# BatMeas5_3_JST.net
KiCad netlist of a schematic drawn in EAGLE
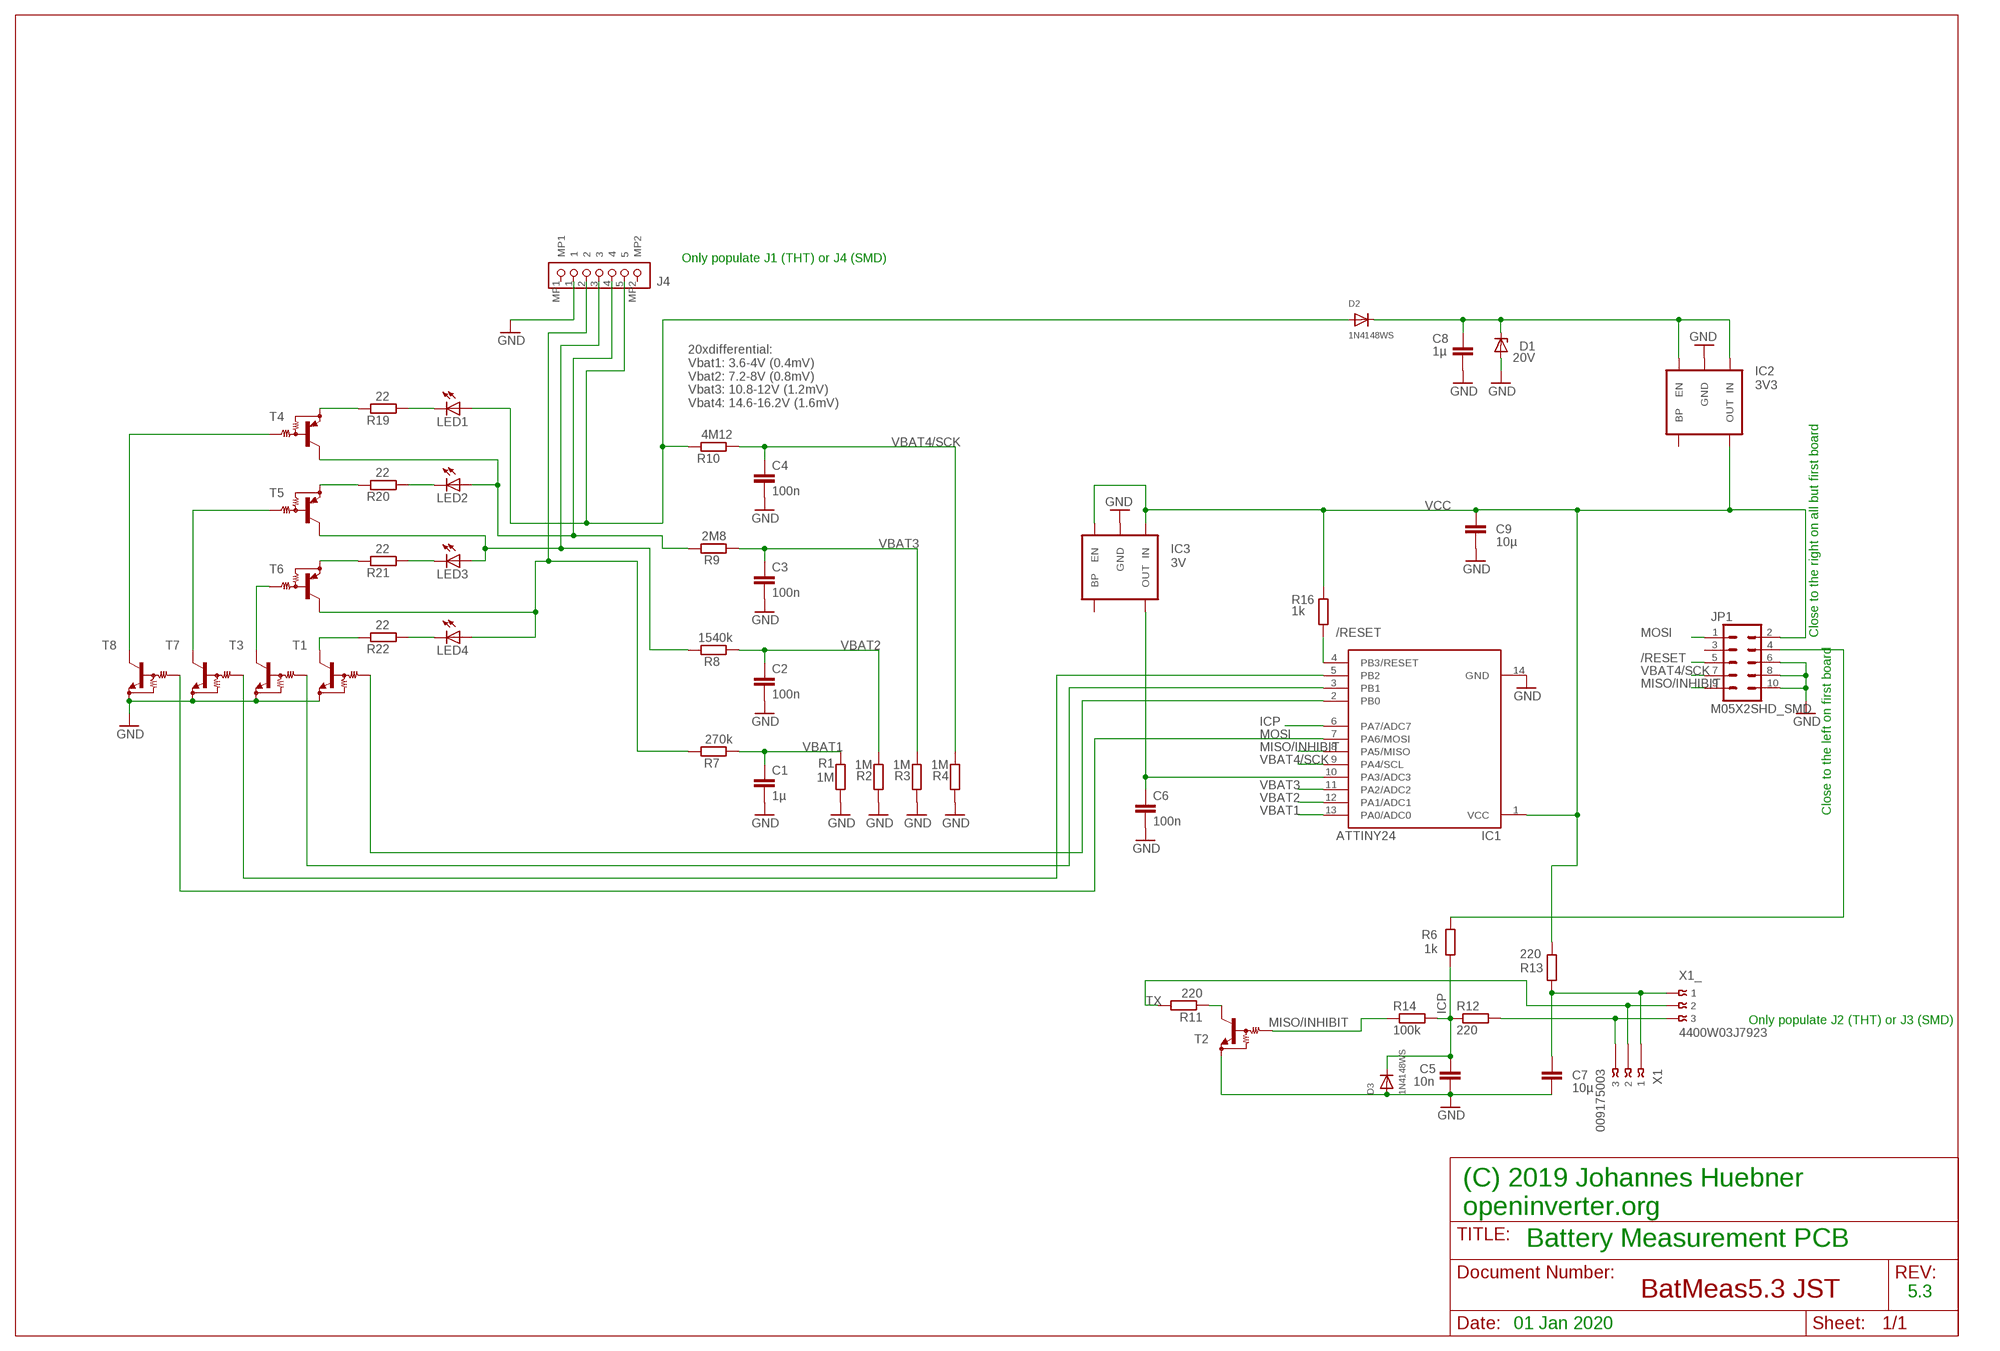
[diagram p0: schematic, sheet 1]

(export (version "E")
  (design (tool "Eeschema 10.0.6"))
  (components
    (comp (ref "C1")
      (value "1µ")
      (footprint "eagle-import:C0603")
      (libsource (lib "eagle-import") (part "C-EUC0603"))
    )
    (comp (ref "C2")
      (value "100n")
      (footprint "eagle-import:C0603")
      (libsource (lib "eagle-import") (part "C-EUC0603"))
    )
    (comp (ref "C3")
      (value "100n")
      (footprint "eagle-import:C0603")
      (libsource (lib "eagle-import") (part "C-EUC0603"))
    )
    (comp (ref "C4")
      (value "100n")
      (footprint "eagle-import:C0603")
      (libsource (lib "eagle-import") (part "C-EUC0603"))
    )
    (comp (ref "C5")
      (value "10n")
      (footprint "eagle-import:C0603")
      (libsource (lib "eagle-import") (part "C-EUC0603"))
    )
    (comp (ref "C6")
      (value "100n")
      (footprint "eagle-import:C0603")
      (libsource (lib "eagle-import") (part "C-EUC0603"))
    )
    (comp (ref "C7")
      (value "10µ")
      (footprint "eagle-import:C0805")
      (libsource (lib "eagle-import") (part "C-EUC0805"))
    )
    (comp (ref "C8")
      (value "1µ")
      (footprint "eagle-import:C0805")
      (libsource (lib "eagle-import") (part "C-EUC0805"))
    )
    (comp (ref "C9")
      (value "10µ")
      (footprint "eagle-import:C0805")
      (libsource (lib "eagle-import") (part "C-EUC0805"))
    )
    (comp (ref "D1")
      (value "20V")
      (footprint "eagle-import:SMB")
      (libsource (lib "eagle-import") (part "ZENER-DIODESMB"))
    )
    (comp (ref "D2")
      (value "1N4148WS")
      (footprint "eagle-import:SOD-323F")
      (libsource (lib "eagle-import") (part "DIODESOD-323F"))
    )
    (comp (ref "D3")
      (value "1N4148WS")
      (footprint "eagle-import:SOD-323F")
      (libsource (lib "eagle-import") (part "DIODESOD-323F"))
    )
    (comp (ref "IC1")
      (value "ATTINY24")
      (footprint "eagle-import:SO014")
      (libsource (lib "eagle-import") (part "ATTINY24"))
    )
    (comp (ref "IC2")
      (value "3V3")
      (footprint "eagle-import:SOT23-5")
      (libsource (lib "eagle-import") (part "V_REG_LDOSMD"))
    )
    (comp (ref "IC3")
      (value "3V")
      (footprint "eagle-import:SOT23-5")
      (libsource (lib "eagle-import") (part "V_REG_LDOSMD"))
    )
    (comp (ref "J4")
      (value "BM05B-PASS-1-TFT_(LF)(SN)SMD")
      (footprint "eagle-import:BM05BPASS1TFTLFSN")
      (libsource (lib "eagle-import") (part "BM05B-PASS-1-TFT_(LF)(SN)SMD"))
    )
    (comp (ref "JP1")
      (value "M05X2SHD_SMD")
      (footprint "eagle-import:2X5-SHROUDED_SMD")
      (libsource (lib "eagle-import") (part "M05X2SHD_SMD"))
    )
    (comp (ref "LED1")
      (value "150060GS75000")
      (footprint "eagle-import:CHIPLED_0805")
      (libsource (lib "eagle-import") (part "LEDCHIPLED_0805"))
    )
    (comp (ref "LED2")
      (value "150060GS75000")
      (footprint "eagle-import:CHIPLED_0805")
      (libsource (lib "eagle-import") (part "LEDCHIPLED_0805"))
    )
    (comp (ref "LED3")
      (value "150060GS75000")
      (footprint "eagle-import:CHIPLED_0805")
      (libsource (lib "eagle-import") (part "LEDCHIPLED_0805"))
    )
    (comp (ref "LED4")
      (value "150060GS75000")
      (footprint "eagle-import:CHIPLED_0805")
      (libsource (lib "eagle-import") (part "LEDCHIPLED_0805"))
    )
    (comp (ref "R1")
      (value "1M")
      (footprint "eagle-import:R0603")
      (libsource (lib "eagle-import") (part "R-EU_R0603"))
    )
    (comp (ref "R2")
      (value "1M")
      (footprint "eagle-import:R0603")
      (libsource (lib "eagle-import") (part "R-EU_R0603"))
    )
    (comp (ref "R3")
      (value "1M")
      (footprint "eagle-import:R0603")
      (libsource (lib "eagle-import") (part "R-EU_R0603"))
    )
    (comp (ref "R4")
      (value "1M")
      (footprint "eagle-import:R0603")
      (libsource (lib "eagle-import") (part "R-EU_R0603"))
    )
    (comp (ref "R6")
      (value "1k")
      (footprint "eagle-import:R0603")
      (libsource (lib "eagle-import") (part "R-EU_R0603"))
    )
    (comp (ref "R7")
      (value "270k")
      (footprint "eagle-import:R0603")
      (libsource (lib "eagle-import") (part "R-EU_R0603"))
    )
    (comp (ref "R8")
      (value "1540k")
      (footprint "eagle-import:R0603")
      (libsource (lib "eagle-import") (part "R-EU_R0603"))
    )
    (comp (ref "R9")
      (value "2M8")
      (footprint "eagle-import:R0603")
      (libsource (lib "eagle-import") (part "R-EU_R0603"))
    )
    (comp (ref "R10")
      (value "4M12")
      (footprint "eagle-import:R0603")
      (libsource (lib "eagle-import") (part "R-EU_R0603"))
    )
    (comp (ref "R11")
      (value "220")
      (footprint "eagle-import:R0603")
      (libsource (lib "eagle-import") (part "R-EU_R0603"))
    )
    (comp (ref "R12")
      (value "220")
      (footprint "eagle-import:R0603")
      (libsource (lib "eagle-import") (part "R-EU_R0603"))
    )
    (comp (ref "R13")
      (value "220")
      (footprint "eagle-import:R0603")
      (libsource (lib "eagle-import") (part "R-EU_R0603"))
    )
    (comp (ref "R14")
      (value "100k")
      (footprint "eagle-import:R0603")
      (libsource (lib "eagle-import") (part "R-EU_R0603"))
    )
    (comp (ref "R16")
      (value "1k")
      (footprint "eagle-import:R0603")
      (libsource (lib "eagle-import") (part "R-EU_R0603"))
    )
    (comp (ref "R19")
      (value "22")
      (footprint "eagle-import:R0805")
      (libsource (lib "eagle-import") (part "R-EU_R0805"))
    )
    (comp (ref "R20")
      (value "22")
      (footprint "eagle-import:R0805")
      (libsource (lib "eagle-import") (part "R-EU_R0805"))
    )
    (comp (ref "R21")
      (value "22")
      (footprint "eagle-import:R0805")
      (libsource (lib "eagle-import") (part "R-EU_R0805"))
    )
    (comp (ref "R22")
      (value "22")
      (footprint "eagle-import:R0805")
      (libsource (lib "eagle-import") (part "R-EU_R0805"))
    )
    (comp (ref "T1")
      (value "MMUN2233")
      (footprint "eagle-import:SC59-BEC")
      (libsource (lib "eagle-import") (part "-NPN_DRIVER-SC59-BECMUN2211T1"))
    )
    (comp (ref "T2")
      (value "MMUN2233")
      (footprint "eagle-import:SC59-BEC")
      (libsource (lib "eagle-import") (part "-NPN_DRIVER-SC59-BECMUN2211T1"))
    )
    (comp (ref "T3")
      (value "MMUN2233")
      (footprint "eagle-import:SC59-BEC")
      (libsource (lib "eagle-import") (part "-NPN_DRIVER-SC59-BECMUN2211T1"))
    )
    (comp (ref "T4")
      (value "MMUN2111LT1G")
      (footprint "eagle-import:SC59-BEC")
      (libsource (lib "eagle-import") (part "-PNP_DRIVER-SC59-BECMUN2111T1"))
    )
    (comp (ref "T5")
      (value "MMUN2111LT1G")
      (footprint "eagle-import:SC59-BEC")
      (libsource (lib "eagle-import") (part "-PNP_DRIVER-SC59-BECMUN2111T1"))
    )
    (comp (ref "T6")
      (value "MMUN2111LT1G")
      (footprint "eagle-import:SC59-BEC")
      (libsource (lib "eagle-import") (part "-PNP_DRIVER-SC59-BECMUN2111T1"))
    )
    (comp (ref "T7")
      (value "MMUN2233")
      (footprint "eagle-import:SC59-BEC")
      (libsource (lib "eagle-import") (part "-NPN_DRIVER-SC59-BECMUN2211T1"))
    )
    (comp (ref "T8")
      (value "MMUN2233")
      (footprint "eagle-import:SC59-BEC")
      (libsource (lib "eagle-import") (part "-NPN_DRIVER-SC59-BECMUN2211T1"))
    )
    (comp (ref "X1")
      (value "009175003")
      (footprint "eagle-import:009175003")
      (fields (field (name "MPN") "009175003001006"))
      (libsource (lib "eagle-import") (part "009175003"))
    )
    (comp (ref "X1_")
      (value "4400W03J7923")
      (footprint "eagle-import:4400WXXJ7923")
      (libsource (lib "eagle-import") (part "4400W03J7923"))
    )
  )
  (nets
    (net (code "1") (name "/ICP") (class "Default")
      (node (ref "C5") (pin "1") (pinfunction "1_1") (pintype "passive"))
      (node (ref "D3") (pin "C") (pinfunction "C_C") (pintype "passive"))
      (node (ref "IC1") (pin "6") (pinfunction "PA7/ADC7_6") (pintype "bidirectional"))
      (node (ref "R12") (pin "1") (pinfunction "1_1") (pintype "passive"))
      (node (ref "R14") (pin "2") (pinfunction "2_2") (pintype "passive"))
      (node (ref "R6") (pin "1") (pinfunction "1_1") (pintype "passive"))
    )
    (net (code "2") (name "/MISO{slash}INHIBIT") (class "Default")
      (node (ref "IC1") (pin "8") (pinfunction "PA5/MISO_8") (pintype "bidirectional"))
      (node (ref "JP1") (pin "9") (pinfunction "9_9") (pintype "passive"))
      (node (ref "R14") (pin "1") (pinfunction "1_1") (pintype "passive"))
      (node (ref "T2") (pin "B") (pinfunction "B_B") (pintype "passive"))
    )
    (net (code "3") (name "/MOSI") (class "Default")
      (node (ref "IC1") (pin "7") (pinfunction "PA6/MOSI_7") (pintype "bidirectional"))
      (node (ref "JP1") (pin "1") (pinfunction "1_1") (pintype "passive"))
      (node (ref "T8") (pin "B") (pinfunction "B_B") (pintype "passive"))
    )
    (net (code "4") (name "/TX") (class "Default")
      (node (ref "R11") (pin "2") (pinfunction "2_2") (pintype "passive"))
      (node (ref "X1") (pin "2@1") (pinfunction "2_2@1") (pintype "passive"))
      (node (ref "X1_") (pin "P$2") (pinfunction "2_P$2") (pintype "passive"))
    )
    (net (code "5") (name "/VBAT1") (class "Default")
      (node (ref "C1") (pin "1") (pinfunction "1_1") (pintype "passive"))
      (node (ref "IC1") (pin "13") (pinfunction "PA0/ADC0_13") (pintype "bidirectional"))
      (node (ref "R1") (pin "1") (pinfunction "1_1") (pintype "passive"))
      (node (ref "R7") (pin "1") (pinfunction "1_1") (pintype "passive"))
    )
    (net (code "6") (name "/VBAT2") (class "Default")
      (node (ref "C2") (pin "1") (pinfunction "1_1") (pintype "passive"))
      (node (ref "IC1") (pin "12") (pinfunction "PA1/ADC1_12") (pintype "bidirectional"))
      (node (ref "R2") (pin "1") (pinfunction "1_1") (pintype "passive"))
      (node (ref "R8") (pin "1") (pinfunction "1_1") (pintype "passive"))
    )
    (net (code "7") (name "/VBAT3") (class "Default")
      (node (ref "C3") (pin "1") (pinfunction "1_1") (pintype "passive"))
      (node (ref "IC1") (pin "11") (pinfunction "PA2/ADC2_11") (pintype "bidirectional"))
      (node (ref "R3") (pin "1") (pinfunction "1_1") (pintype "passive"))
      (node (ref "R9") (pin "1") (pinfunction "1_1") (pintype "passive"))
    )
    (net (code "8") (name "/VBAT4{slash}SCK") (class "Default")
      (node (ref "C4") (pin "1") (pinfunction "1_1") (pintype "passive"))
      (node (ref "IC1") (pin "9") (pinfunction "PA4/SCL_9") (pintype "bidirectional"))
      (node (ref "JP1") (pin "7") (pinfunction "7_7") (pintype "passive"))
      (node (ref "R10") (pin "1") (pinfunction "1_1") (pintype "passive"))
      (node (ref "R4") (pin "1") (pinfunction "1_1") (pintype "passive"))
    )
    (net (code "9") (name "/VCC") (class "Default")
      (node (ref "C9") (pin "1") (pinfunction "1_1") (pintype "passive"))
      (node (ref "IC1") (pin "1") (pinfunction "VCC_1") (pintype "bidirectional"))
      (node (ref "IC2") (pin "5") (pinfunction "OUT_5") (pintype "passive"))
      (node (ref "IC3") (pin "1") (pinfunction "IN_1") (pintype "input"))
      (node (ref "IC3") (pin "3") (pinfunction "EN_3") (pintype "input"))
      (node (ref "JP1") (pin "2") (pinfunction "2_2") (pintype "passive"))
      (node (ref "R13") (pin "1") (pinfunction "1_1") (pintype "passive"))
      (node (ref "R16") (pin "1") (pinfunction "1_1") (pintype "passive"))
    )
    (net (code "10") (name "/{slash}RESET") (class "Default")
      (node (ref "IC1") (pin "4") (pinfunction "PB3/RESET_4") (pintype "bidirectional"))
      (node (ref "JP1") (pin "5") (pinfunction "5_5") (pintype "passive"))
      (node (ref "R16") (pin "2") (pinfunction "2_2") (pintype "passive"))
    )
    (net (code "11") (name "GND") (class "Default")
      (node (ref "C1") (pin "2") (pinfunction "2_2") (pintype "passive"))
      (node (ref "C2") (pin "2") (pinfunction "2_2") (pintype "passive"))
      (node (ref "C3") (pin "2") (pinfunction "2_2") (pintype "passive"))
      (node (ref "C4") (pin "2") (pinfunction "2_2") (pintype "passive"))
      (node (ref "C5") (pin "2") (pinfunction "2_2") (pintype "passive"))
      (node (ref "C6") (pin "2") (pinfunction "2_2") (pintype "passive"))
      (node (ref "C7") (pin "2") (pinfunction "2_2") (pintype "passive"))
      (node (ref "C8") (pin "2") (pinfunction "2_2") (pintype "passive"))
      (node (ref "C9") (pin "2") (pinfunction "2_2") (pintype "passive"))
      (node (ref "D1") (pin "A") (pinfunction "A_A") (pintype "passive"))
      (node (ref "D3") (pin "A") (pinfunction "A_A") (pintype "passive"))
      (node (ref "IC1") (pin "14") (pinfunction "GND_14") (pintype "bidirectional"))
      (node (ref "IC2") (pin "2") (pinfunction "GND_2") (pintype "input"))
      (node (ref "IC3") (pin "2") (pinfunction "GND_2") (pintype "input"))
      (node (ref "J4") (pin "1") (pinfunction "1_1") (pintype "bidirectional"))
      (node (ref "JP1") (pin "10") (pinfunction "10_10") (pintype "passive"))
      (node (ref "JP1") (pin "6") (pinfunction "6_6") (pintype "passive"))
      (node (ref "JP1") (pin "8") (pinfunction "8_8") (pintype "passive"))
      (node (ref "R1") (pin "2") (pinfunction "2_2") (pintype "passive"))
      (node (ref "R2") (pin "2") (pinfunction "2_2") (pintype "passive"))
      (node (ref "R3") (pin "2") (pinfunction "2_2") (pintype "passive"))
      (node (ref "R4") (pin "2") (pinfunction "2_2") (pintype "passive"))
      (node (ref "T1") (pin "E") (pinfunction "E_E") (pintype "passive"))
      (node (ref "T2") (pin "E") (pinfunction "E_E") (pintype "passive"))
      (node (ref "T3") (pin "E") (pinfunction "E_E") (pintype "passive"))
      (node (ref "T7") (pin "E") (pinfunction "E_E") (pintype "passive"))
      (node (ref "T8") (pin "E") (pinfunction "E_E") (pintype "passive"))
    )
    (net (code "12") (name "Net-(D2-PadA)") (class "Default")
      (node (ref "D2") (pin "A") (pinfunction "A_A") (pintype "passive"))
      (node (ref "J4") (pin "5") (pinfunction "5_5") (pintype "bidirectional"))
      (node (ref "LED1") (pin "A") (pinfunction "A_A") (pintype "passive"))
      (node (ref "R10") (pin "2") (pinfunction "2_2") (pintype "passive"))
    )
    (net (code "13") (name "Net-(IC1-PA3{slash}ADC3)") (class "Default")
      (node (ref "C6") (pin "1") (pinfunction "1_1") (pintype "passive"))
      (node (ref "IC1") (pin "10") (pinfunction "PA3/ADC3_10") (pintype "bidirectional"))
      (node (ref "IC3") (pin "5") (pinfunction "OUT_5") (pintype "passive"))
    )
    (net (code "14") (name "Net-(IC1-PB0)") (class "Default")
      (node (ref "IC1") (pin "2") (pinfunction "PB0_2") (pintype "bidirectional"))
      (node (ref "T1") (pin "B") (pinfunction "B_B") (pintype "passive"))
    )
    (net (code "15") (name "Net-(IC1-PB1)") (class "Default")
      (node (ref "IC1") (pin "3") (pinfunction "PB1_3") (pintype "bidirectional"))
      (node (ref "T3") (pin "B") (pinfunction "B_B") (pintype "passive"))
    )
    (net (code "16") (name "Net-(IC1-PB2)") (class "Default")
      (node (ref "IC1") (pin "5") (pinfunction "PB2_5") (pintype "bidirectional"))
      (node (ref "T7") (pin "B") (pinfunction "B_B") (pintype "passive"))
    )
    (net (code "17") (name "Net-(IC2-EN)") (class "Default")
      (node (ref "C8") (pin "1") (pinfunction "1_1") (pintype "passive"))
      (node (ref "D1") (pin "C") (pinfunction "C_C") (pintype "passive"))
      (node (ref "D2") (pin "C") (pinfunction "C_C") (pintype "passive"))
      (node (ref "IC2") (pin "1") (pinfunction "IN_1") (pintype "input"))
      (node (ref "IC2") (pin "3") (pinfunction "EN_3") (pintype "input"))
    )
    (net (code "18") (name "Net-(J4-Pad2)") (class "Default")
      (node (ref "J4") (pin "2") (pinfunction "2_2") (pintype "bidirectional"))
      (node (ref "LED4") (pin "A") (pinfunction "A_A") (pintype "passive"))
      (node (ref "R7") (pin "2") (pinfunction "2_2") (pintype "passive"))
      (node (ref "T6") (pin "C") (pinfunction "C_C") (pintype "passive"))
    )
    (net (code "19") (name "Net-(J4-Pad3)") (class "Default")
      (node (ref "J4") (pin "3") (pinfunction "3_3") (pintype "bidirectional"))
      (node (ref "LED3") (pin "A") (pinfunction "A_A") (pintype "passive"))
      (node (ref "R8") (pin "2") (pinfunction "2_2") (pintype "passive"))
      (node (ref "T5") (pin "C") (pinfunction "C_C") (pintype "passive"))
    )
    (net (code "20") (name "Net-(J4-Pad4)") (class "Default")
      (node (ref "J4") (pin "4") (pinfunction "4_4") (pintype "bidirectional"))
      (node (ref "LED2") (pin "A") (pinfunction "A_A") (pintype "passive"))
      (node (ref "R9") (pin "2") (pinfunction "2_2") (pintype "passive"))
      (node (ref "T4") (pin "C") (pinfunction "C_C") (pintype "passive"))
    )
    (net (code "21") (name "Net-(JP1-Pad4)") (class "Default")
      (node (ref "JP1") (pin "4") (pinfunction "4_4") (pintype "passive"))
      (node (ref "R6") (pin "2") (pinfunction "2_2") (pintype "passive"))
    )
    (net (code "22") (name "Net-(LED1-PadC)") (class "Default")
      (node (ref "LED1") (pin "C") (pinfunction "C_C") (pintype "passive"))
      (node (ref "R19") (pin "1") (pinfunction "1_1") (pintype "passive"))
    )
    (net (code "23") (name "Net-(LED2-PadC)") (class "Default")
      (node (ref "LED2") (pin "C") (pinfunction "C_C") (pintype "passive"))
      (node (ref "R20") (pin "1") (pinfunction "1_1") (pintype "passive"))
    )
    (net (code "24") (name "Net-(LED3-PadC)") (class "Default")
      (node (ref "LED3") (pin "C") (pinfunction "C_C") (pintype "passive"))
      (node (ref "R21") (pin "1") (pinfunction "1_1") (pintype "passive"))
    )
    (net (code "25") (name "Net-(LED4-PadC)") (class "Default")
      (node (ref "LED4") (pin "C") (pinfunction "C_C") (pintype "passive"))
      (node (ref "R22") (pin "1") (pinfunction "1_1") (pintype "passive"))
    )
    (net (code "26") (name "Net-(R11-Pad1)") (class "Default")
      (node (ref "R11") (pin "1") (pinfunction "1_1") (pintype "passive"))
      (node (ref "T2") (pin "C") (pinfunction "C_C") (pintype "passive"))
    )
    (net (code "27") (name "Net-(R19-Pad2)") (class "Default")
      (node (ref "R19") (pin "2") (pinfunction "2_2") (pintype "passive"))
      (node (ref "T4") (pin "E") (pinfunction "E_E") (pintype "passive"))
    )
    (net (code "28") (name "Net-(R20-Pad2)") (class "Default")
      (node (ref "R20") (pin "2") (pinfunction "2_2") (pintype "passive"))
      (node (ref "T5") (pin "E") (pinfunction "E_E") (pintype "passive"))
    )
    (net (code "29") (name "Net-(R21-Pad2)") (class "Default")
      (node (ref "R21") (pin "2") (pinfunction "2_2") (pintype "passive"))
      (node (ref "T6") (pin "E") (pinfunction "E_E") (pintype "passive"))
    )
    (net (code "30") (name "Net-(R22-Pad2)") (class "Default")
      (node (ref "R22") (pin "2") (pinfunction "2_2") (pintype "passive"))
      (node (ref "T1") (pin "C") (pinfunction "C_C") (pintype "passive"))
    )
    (net (code "31") (name "Net-(T3-PadC)") (class "Default")
      (node (ref "T3") (pin "C") (pinfunction "C_C") (pintype "passive"))
      (node (ref "T6") (pin "B") (pinfunction "B_B") (pintype "passive"))
    )
    (net (code "32") (name "Net-(T4-PadB)") (class "Default")
      (node (ref "T4") (pin "B") (pinfunction "B_B") (pintype "passive"))
      (node (ref "T8") (pin "C") (pinfunction "C_C") (pintype "passive"))
    )
    (net (code "33") (name "Net-(T5-PadB)") (class "Default")
      (node (ref "T5") (pin "B") (pinfunction "B_B") (pintype "passive"))
      (node (ref "T7") (pin "C") (pinfunction "C_C") (pintype "passive"))
    )
    (net (code "34") (name "Net-(X1_-1)") (class "Default")
      (node (ref "C7") (pin "1") (pinfunction "1_1") (pintype "passive"))
      (node (ref "R13") (pin "2") (pinfunction "2_2") (pintype "passive"))
      (node (ref "X1") (pin "1@1") (pinfunction "1_1@1") (pintype "passive"))
      (node (ref "X1_") (pin "P$1") (pinfunction "1_P$1") (pintype "passive"))
    )
    (net (code "35") (name "Net-(X1_-3)") (class "Default")
      (node (ref "R12") (pin "2") (pinfunction "2_2") (pintype "passive"))
      (node (ref "X1") (pin "3@2") (pinfunction "3_3@2") (pintype "passive"))
      (node (ref "X1_") (pin "P$3") (pinfunction "3_P$3") (pintype "passive"))
    )
    (net (code "36") (name "unconnected-(IC2-BP-Pad4)") (class "Default")
      (node (ref "IC2") (pin "4") (pinfunction "BP_4") (pintype "input"))
    )
    (net (code "37") (name "unconnected-(IC3-BP-Pad4)") (class "Default")
      (node (ref "IC3") (pin "4") (pinfunction "BP_4") (pintype "input"))
    )
    (net (code "38") (name "unconnected-(J4-PadMP1)") (class "Default")
      (node (ref "J4") (pin "MP1") (pinfunction "MP1_MP1") (pintype "bidirectional"))
    )
    (net (code "39") (name "unconnected-(J4-PadMP2)") (class "Default")
      (node (ref "J4") (pin "MP2") (pinfunction "MP2_MP2") (pintype "bidirectional"))
    )
    (net (code "40") (name "unconnected-(JP1-Pad3)") (class "Default")
      (node (ref "JP1") (pin "3") (pinfunction "3_3") (pintype "passive"))
    )
    (net (code "41") (name "unconnected-(X1-Pad1)") (class "Default")
      (node (ref "X1") (pin "1") (pinfunction "1_1") (pintype "passive"))
    )
    (net (code "42") (name "unconnected-(X1-Pad2)") (class "Default")
      (node (ref "X1") (pin "2") (pinfunction "2_2") (pintype "passive"))
    )
    (net (code "43") (name "unconnected-(X1-Pad3)") (class "Default")
      (node (ref "X1") (pin "3") (pinfunction "3_3") (pintype "passive"))
    )
  )
)
